# 4D_sampling_head.net
KiCad netlist of a schematic drawn in EAGLE
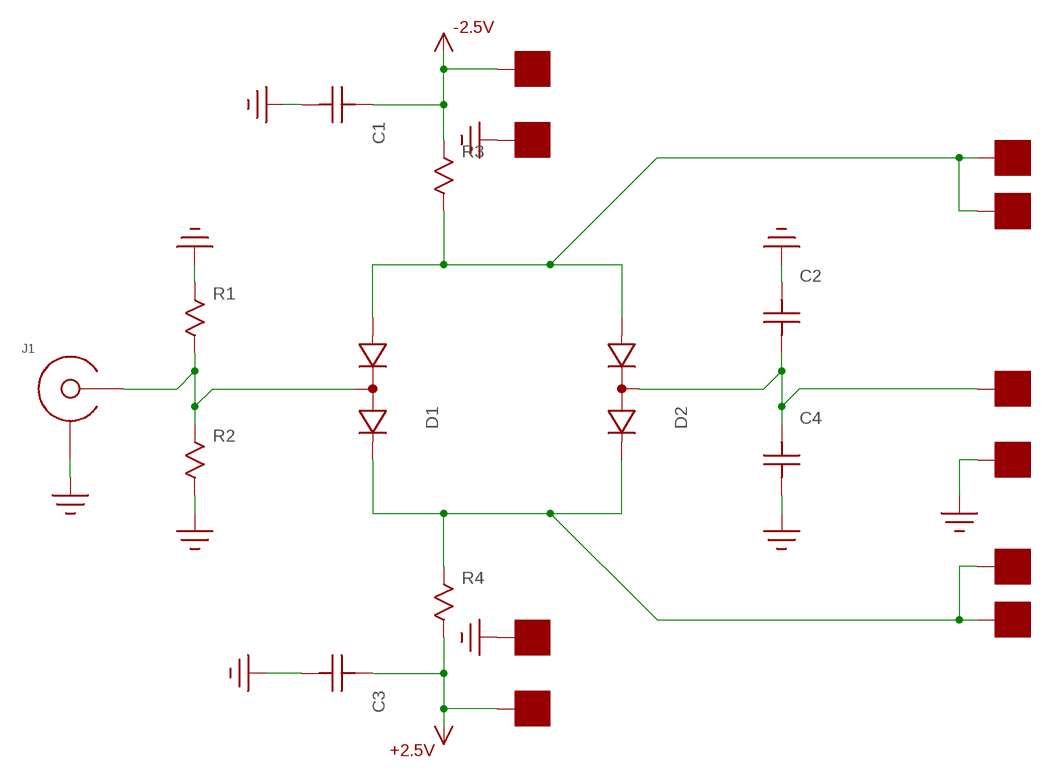
[diagram p0: schematic, sheet 1]

(export (version "E")
  (design (tool "Eeschema 10.0.6"))
  (components
    (comp (ref "C1")
      (value "C0603")
      (footprint "eagle-import:C0603")
      (libsource (lib "eagle-import") (part "C0603"))
    )
    (comp (ref "C2")
      (value "C0603")
      (footprint "eagle-import:C0603")
      (libsource (lib "eagle-import") (part "C0603"))
    )
    (comp (ref "C3")
      (value "C0603")
      (footprint "eagle-import:C0603")
      (libsource (lib "eagle-import") (part "C0603"))
    )
    (comp (ref "C4")
      (value "C0603")
      (footprint "eagle-import:C0603")
      (libsource (lib "eagle-import") (part "C0603"))
    )
    (comp (ref "D1")
      (value "MMBD352LT1G")
      (footprint "eagle-import:SOT-23")
      (libsource (lib "eagle-import") (part "MMBD352LT1G"))
    )
    (comp (ref "D2")
      (value "MMBD353LT1G")
      (footprint "eagle-import:SOT-23")
      (libsource (lib "eagle-import") (part "MMBD353LT1G"))
    )
    (comp (ref "J1")
      (value "EDGE_LAUNCH_JACK")
      (footprint "eagle-import:EDGE_LAUNCH_RF_CON")
      (libsource (lib "eagle-import") (part "EDGE_LAUNCH_JACK"))
    )
    (comp (ref "R1")
      (value "R0603")
      (footprint "eagle-import:R0603")
      (libsource (lib "eagle-import") (part "R0603"))
    )
    (comp (ref "R2")
      (value "R0603")
      (footprint "eagle-import:R0603")
      (libsource (lib "eagle-import") (part "R0603"))
    )
    (comp (ref "R3")
      (value "R0603")
      (footprint "eagle-import:R0603")
      (libsource (lib "eagle-import") (part "R0603"))
    )
    (comp (ref "R4")
      (value "R0603")
      (footprint "eagle-import:R0603")
      (libsource (lib "eagle-import") (part "R0603"))
    )
    (comp (ref "U$11")
      (value "PAD50MIL")
      (footprint "eagle-import:PAD_50MIL")
      (libsource (lib "eagle-import") (part "PAD50MIL"))
    )
    (comp (ref "U$12")
      (value "PAD50MIL")
      (footprint "eagle-import:PAD_50MIL")
      (libsource (lib "eagle-import") (part "PAD50MIL"))
    )
    (comp (ref "U$13")
      (value "PAD50MIL")
      (footprint "eagle-import:PAD_50MIL")
      (libsource (lib "eagle-import") (part "PAD50MIL"))
    )
    (comp (ref "U$14")
      (value "PAD50MIL")
      (footprint "eagle-import:PAD_50MIL")
      (libsource (lib "eagle-import") (part "PAD50MIL"))
    )
    (comp (ref "U$15")
      (value "PAD100MIL")
      (footprint "eagle-import:PAD_100MIL")
      (libsource (lib "eagle-import") (part "PAD100MIL"))
    )
    (comp (ref "U$16")
      (value "PAD100MIL")
      (footprint "eagle-import:PAD_100MIL")
      (libsource (lib "eagle-import") (part "PAD100MIL"))
    )
    (comp (ref "U$18")
      (value "PAD100MIL")
      (footprint "eagle-import:PAD_100MIL")
      (libsource (lib "eagle-import") (part "PAD100MIL"))
    )
    (comp (ref "U$19")
      (value "PAD100MIL")
      (footprint "eagle-import:PAD_100MIL")
      (libsource (lib "eagle-import") (part "PAD100MIL"))
    )
    (comp (ref "U$20")
      (value "PAD100MIL")
      (footprint "eagle-import:PAD_100MIL")
      (libsource (lib "eagle-import") (part "PAD100MIL"))
    )
    (comp (ref "U$21")
      (value "PAD100MIL")
      (footprint "eagle-import:PAD_100MIL")
      (libsource (lib "eagle-import") (part "PAD100MIL"))
    )
  )
  (nets
    (net (code "1") (name "+2.5V") (class "Default")
      (node (ref "C3") (pin "P$2") (pinfunction "P$2_P$2") (pintype "bidirectional"))
      (node (ref "R4") (pin "P$2") (pinfunction "P$4_P$2") (pintype "bidirectional"))
      (node (ref "U$19") (pin "P$1") (pinfunction "P$1_P$1") (pintype "bidirectional"))
    )
    (net (code "2") (name "-2.5V") (class "Default")
      (node (ref "C1") (pin "P$2") (pinfunction "P$2_P$2") (pintype "bidirectional"))
      (node (ref "R3") (pin "P$1") (pinfunction "P$3_P$1") (pintype "bidirectional"))
      (node (ref "U$18") (pin "P$1") (pinfunction "P$1_P$1") (pintype "bidirectional"))
    )
    (net (code "3") (name "GND") (class "Default")
      (node (ref "C1") (pin "P$1") (pinfunction "P$1_P$1") (pintype "bidirectional"))
      (node (ref "C2") (pin "P$2") (pinfunction "P$2_P$2") (pintype "bidirectional"))
      (node (ref "C3") (pin "P$1") (pinfunction "P$1_P$1") (pintype "bidirectional"))
      (node (ref "C4") (pin "P$1") (pinfunction "P$1_P$1") (pintype "bidirectional"))
      (node (ref "J1") (pin "GND@1") (pinfunction "SHIELD_GND@1") (pintype "bidirectional"))
      (node (ref "J1") (pin "GND@10") (pinfunction "SHIELD_GND@10") (pintype "bidirectional"))
      (node (ref "J1") (pin "GND@11") (pinfunction "SHIELD_GND@11") (pintype "bidirectional"))
      (node (ref "J1") (pin "GND@12") (pinfunction "SHIELD_GND@12") (pintype "bidirectional"))
      (node (ref "J1") (pin "GND@2") (pinfunction "SHIELD_GND@2") (pintype "bidirectional"))
      (node (ref "J1") (pin "GND@3") (pinfunction "SHIELD_GND@3") (pintype "bidirectional"))
      (node (ref "J1") (pin "GND@4") (pinfunction "SHIELD_GND@4") (pintype "bidirectional"))
      (node (ref "J1") (pin "GND@5") (pinfunction "SHIELD_GND@5") (pintype "bidirectional"))
      (node (ref "J1") (pin "GND@6") (pinfunction "SHIELD_GND@6") (pintype "bidirectional"))
      (node (ref "J1") (pin "GND@7") (pinfunction "SHIELD_GND@7") (pintype "bidirectional"))
      (node (ref "J1") (pin "GND@8") (pinfunction "SHIELD_GND@8") (pintype "bidirectional"))
      (node (ref "J1") (pin "GND@9") (pinfunction "SHIELD_GND@9") (pintype "bidirectional"))
      (node (ref "J1") (pin "SHIELD@1") (pinfunction "SHIELD_SHIELD@1") (pintype "bidirectional"))
      (node (ref "J1") (pin "SHIELD@2") (pinfunction "SHIELD_SHIELD@2") (pintype "bidirectional"))
      (node (ref "R1") (pin "P$1") (pinfunction "P$3_P$1") (pintype "bidirectional"))
      (node (ref "R2") (pin "P$2") (pinfunction "P$4_P$2") (pintype "bidirectional"))
      (node (ref "U$16") (pin "P$1") (pinfunction "P$1_P$1") (pintype "bidirectional"))
      (node (ref "U$20") (pin "P$1") (pinfunction "P$1_P$1") (pintype "bidirectional"))
      (node (ref "U$21") (pin "P$1") (pinfunction "P$1_P$1") (pintype "bidirectional"))
    )
    (net (code "4") (name "Net-(D1-ANODE)") (class "Default")
      (node (ref "D1") (pin "1") (pinfunction "ANODE_1") (pintype "bidirectional"))
      (node (ref "D2") (pin "2") (pinfunction "ANODE_2") (pintype "bidirectional"))
      (node (ref "R3") (pin "P$2") (pinfunction "P$4_P$2") (pintype "bidirectional"))
      (node (ref "U$11") (pin "P$1") (pinfunction "P$1_P$1") (pintype "bidirectional"))
      (node (ref "U$13") (pin "P$1") (pinfunction "P$1_P$1") (pintype "bidirectional"))
    )
    (net (code "5") (name "Net-(D1-CATHODE)") (class "Default")
      (node (ref "D1") (pin "2") (pinfunction "CATHODE_2") (pintype "bidirectional"))
      (node (ref "D2") (pin "1") (pinfunction "CATHODE_1") (pintype "bidirectional"))
      (node (ref "R4") (pin "P$1") (pinfunction "P$3_P$1") (pintype "bidirectional"))
      (node (ref "U$12") (pin "P$1") (pinfunction "P$1_P$1") (pintype "bidirectional"))
      (node (ref "U$14") (pin "P$1") (pinfunction "P$1_P$1") (pintype "bidirectional"))
    )
    (net (code "6") (name "Net-(D1-COMMON)") (class "Default")
      (node (ref "D1") (pin "3") (pinfunction "COMMON_3") (pintype "bidirectional"))
      (node (ref "J1") (pin "CENTER") (pinfunction "CENTER_CENTER") (pintype "bidirectional"))
      (node (ref "R1") (pin "P$2") (pinfunction "P$4_P$2") (pintype "bidirectional"))
      (node (ref "R2") (pin "P$1") (pinfunction "P$3_P$1") (pintype "bidirectional"))
    )
    (net (code "7") (name "Net-(D2-COMMON)") (class "Default")
      (node (ref "C2") (pin "P$1") (pinfunction "P$1_P$1") (pintype "bidirectional"))
      (node (ref "C4") (pin "P$2") (pinfunction "P$2_P$2") (pintype "bidirectional"))
      (node (ref "D2") (pin "3") (pinfunction "COMMON_3") (pintype "bidirectional"))
      (node (ref "U$15") (pin "P$1") (pinfunction "P$1_P$1") (pintype "bidirectional"))
    )
  )
)
